# CANBUS_Pendant.net
KiCad netlist of a schematic drawn in Altium Designer
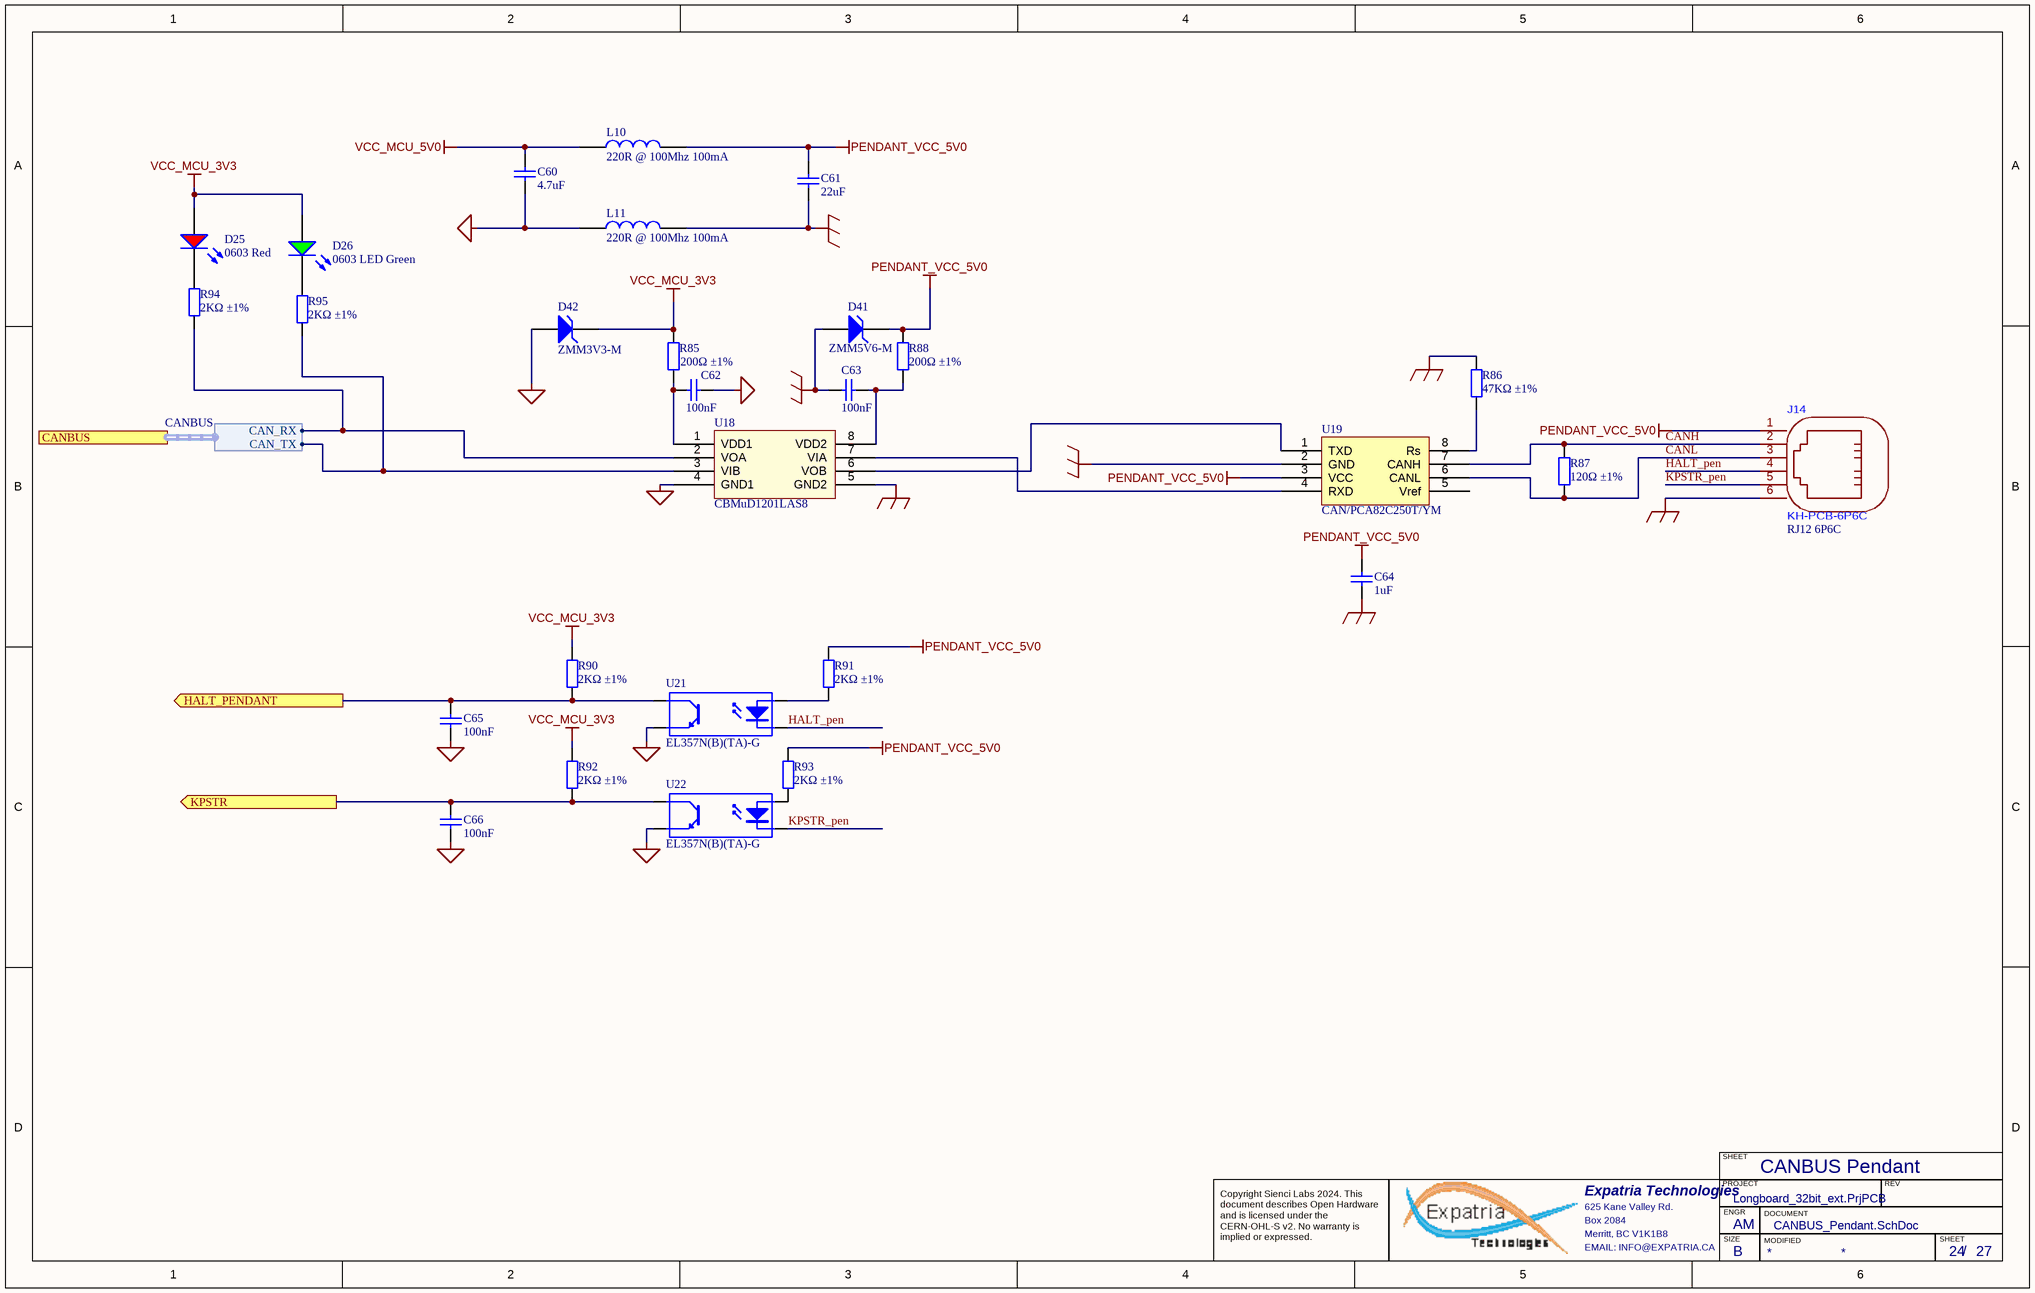
[diagram p0: CANBUS_Pendant.SchDoc]

(export (version "E")
  (design (tool "Eeschema 10.0.6"))
  (components
    (comp (ref "C60")
      (value "4.7uF")
      (footprint "0805_C")
      (description "Chip capacitors")
      (fields
        (field (name "MANUFACTURER") "Samsung Electro-Mechanics")
        (field (name "MANUFACTURER PART NUMBER") "CL21A475KAQNNNE")
      )
      (libsource (lib "Cap") (part "0805 4.7uF (475) 10% 25V"))
    )
    (comp (ref "C61")
      (value "22uF")
      (footprint "0805_C")
      (description "25V 22uF X5R ±20% 0805 Multilayer Ceramic Capacitors MLCC - SMD/SMT ROHS")
      (fields (field (name "MANUFACTURER") "Samsung Electro-Mechanics") (field (name "TOLERANCE") "20%"))
      (libsource (lib "Sienci_Labs") (part "0805 22uF (226) 20% 25V"))
    )
    (comp (ref "C62")
      (value "100nF")
      (footprint "0402_C")
      (description "16V 100nF X7R ±10% 0402 Multilayer Ceramic Capacitors MLCC - SMD/SMT ROHS")
      (fields (field (name "MANUFACTURER") "Samsung Electro-Mechanics") (field (name "TOLERANCE") "10%"))
      (libsource (lib "Sienci_Labs") (part "0402 100nF (104) 10% 16V"))
    )
    (comp (ref "C63")
      (value "100nF")
      (footprint "0402_C")
      (description "16V 100nF X7R ±10% 0402 Multilayer Ceramic Capacitors MLCC - SMD/SMT ROHS")
      (fields (field (name "MANUFACTURER") "Samsung Electro-Mechanics") (field (name "TOLERANCE") "10%"))
      (libsource (lib "Sienci_Labs") (part "0402 100nF (104) 10% 16V"))
    )
    (comp (ref "C64")
      (value "1uF")
      (footprint "0603_C")
      (description "Chip capacitors")
      (fields
        (field (name "MANUFACTURER") "Samsung Electro-Mechanics")
        (field (name "MANUFACTURER PART NUMBER") "CL10A105KB8NNNC")
      )
      (libsource (lib "Cap") (part "0603 1uF (105) 10% 50V"))
    )
    (comp (ref "C65")
      (value "100nF")
      (footprint "0603_C")
      (description "50V 100nF X7R ±10% 0603 Multilayer Ceramic Capacitors MLCC - SMD/SMT ROHS")
      (fields
        (field (name "MANUFACTURER") "YAGEO")
        (field (name "MANUFACTURER PART NUMBER") "CC0603KRX7R9BB104")
      )
      (libsource (lib "Sienci_Labs") (part "0603 100nF (104) 10% 50V"))
    )
    (comp (ref "C66")
      (value "100nF")
      (footprint "0603_C")
      (description "50V 100nF X7R ±10% 0603 Multilayer Ceramic Capacitors MLCC - SMD/SMT ROHS")
      (fields
        (field (name "MANUFACTURER") "YAGEO")
        (field (name "MANUFACTURER PART NUMBER") "CC0603KRX7R9BB104")
      )
      (libsource (lib "Sienci_Labs") (part "0603 100nF (104) 10% 50V"))
    )
    (comp (ref "D25")
      (value "0603 Red")
      (footprint "0603_LED_S1")
      (description "-40℃~+85℃ Red 0603 Light Emitting Diodes (LED) ROHS")
      (fields
        (field (name "MANUFACTURER") "Hubei KENTO Elec")
        (field (name "MANUFACTURER PART NUMBER") "KT-0603R")
      )
      (libsource (lib "Sienci_Labs") (part "KT-0603R"))
    )
    (comp (ref "D26")
      (value "0603 LED Green")
      (footprint "0603_LED_S1 - GREEN")
      (description "20mA -40℃~+85℃ 515nm~530nm Emerald 120° 60mW 0603 Light Emitting Diodes (LED) ROHS")
      (fields (field (name "MANUFACTURER PART NUMBER") "MHT192UGCT") (field (name "MANUFACTURER") "MEIHUA"))
      (libsource (lib "Sienci_Labs") (part "MHT192UGCT"))
    )
    (comp (ref "D41")
      (value "ZMM5V6-M")
      (footprint "LL-34")
      (description "Single 500mW 5.2V~6V 5.6V LL-34 Zener Diodes ROHS")
      (fields (field (name "MANUFACTURER PART NUMBER") "ZMM5V6") (field (name "MANUFACTURER") "HXY MOSFET"))
      (libsource (lib "Sienci_Labs") (part "LL-34 ZMM5V6-M"))
    )
    (comp (ref "D42")
      (value "ZMM3V3-M")
      (footprint "LL-34")
      (description "Single 3.1V~3.5V 500mW 3.3V LL-34 Zener Diodes ROHS")
      (fields (field (name "MANUFACTURER") "ST(Semtech)"))
      (libsource (lib "Sienci_Labs") (part "LL-34 ZMM3V3-M"))
    )
    (comp (ref "J14")
      (value "KH-PCB-6P6C")
      (footprint "RJ11-TH_DS1133-S60BPX")
      (fields
        (field (name "MANUFACTURER") "Shenzhen Kinghelm Elec")
        (field (name "ALTIUM_VALUE") "RJ12 6P6C")
      )
      (libsource (lib "Sienci_Labs") (part "KH-PCB-6P6C"))
    )
    (comp (ref "L10")
      (value "220R @ 100Mhz 100mA")
      (footprint "0402_L")
      (description "700mΩ ±25% 220Ω@100MHz 0402 Ferrite Beads ROHS")
      (fields
        (field (name "MANUFACTURER PART NUMBER") "CBG100505U221T")
        (field (name "MANUFACTURER") "FH (Guangdong Fenghua Advanced Tech)")
      )
      (libsource (lib "Sienci_Labs") (part "0402 220R@100Mhz 0.1A"))
    )
    (comp (ref "L11")
      (value "220R @ 100Mhz 100mA")
      (footprint "0402_L")
      (description "700mΩ ±25% 220Ω@100MHz 0402 Ferrite Beads ROHS")
      (fields
        (field (name "MANUFACTURER PART NUMBER") "CBG100505U221T")
        (field (name "MANUFACTURER") "FH (Guangdong Fenghua Advanced Tech)")
      )
      (libsource (lib "Sienci_Labs") (part "0402 220R@100Mhz 0.1A"))
    )
    (comp (ref "R85")
      (value "200Ω ±1%")
      (footprint "0402_R")
      (description "Chip resistor")
      (fields
        (field (name "MANUFACTURER") "Uniroyal Elec")
        (field (name "MANUFACTURER PART NUMBER") "0402WGF2000TCE")
      )
      (libsource (lib "RES") (part "0402 200R (2000) 1%"))
    )
    (comp (ref "R86")
      (value "47KΩ ±1%")
      (footprint "0402_R")
      (description "Chip resistor")
      (fields
        (field (name "MANUFACTURER") "Uniroyal Elec")
        (field (name "MANUFACTURER PART NUMBER") "0402WGF4702TCE")
      )
      (libsource (lib "RES") (part "0402 47K (4702) 1%"))
    )
    (comp (ref "R87")
      (value "120Ω ±1%")
      (footprint "0805_R")
      (description "Chip resistor")
      (fields
        (field (name "MANUFACTURER") "Uniroyal Elec")
        (field (name "MANUFACTURER PART NUMBER") "0805W8F1200T5E")
      )
      (libsource (lib "RES") (part "0805 120R (1200) 1%"))
    )
    (comp (ref "R88")
      (value "200Ω ±1%")
      (footprint "0402_R")
      (description "Chip resistor")
      (fields
        (field (name "MANUFACTURER") "Uniroyal Elec")
        (field (name "MANUFACTURER PART NUMBER") "0402WGF2000TCE")
      )
      (libsource (lib "RES") (part "0402 200R (2000) 1%"))
    )
    (comp (ref "R90")
      (value "2KΩ ±1%")
      (footprint "0402_R")
      (description "Chip resistor")
      (fields
        (field (name "MANUFACTURER") "Uniroyal Elec")
        (field (name "MANUFACTURER PART NUMBER") "0402WGF2001TCE")
      )
      (libsource (lib "RES") (part "0402 2K (2001) 1%"))
    )
    (comp (ref "R91")
      (value "2KΩ ±1%")
      (footprint "0402_R")
      (description "Chip resistor")
      (fields
        (field (name "MANUFACTURER") "Uniroyal Elec")
        (field (name "MANUFACTURER PART NUMBER") "0402WGF2001TCE")
      )
      (libsource (lib "RES") (part "0402 2K (2001) 1%"))
    )
    (comp (ref "R92")
      (value "2KΩ ±1%")
      (footprint "0402_R")
      (description "Chip resistor")
      (fields
        (field (name "MANUFACTURER") "Uniroyal Elec")
        (field (name "MANUFACTURER PART NUMBER") "0402WGF2001TCE")
      )
      (libsource (lib "RES") (part "0402 2K (2001) 1%"))
    )
    (comp (ref "R93")
      (value "2KΩ ±1%")
      (footprint "0402_R")
      (description "Chip resistor")
      (fields
        (field (name "MANUFACTURER") "Uniroyal Elec")
        (field (name "MANUFACTURER PART NUMBER") "0402WGF2001TCE")
      )
      (libsource (lib "RES") (part "0402 2K (2001) 1%"))
    )
    (comp (ref "R94")
      (value "2KΩ ±1%")
      (footprint "0402_R")
      (description "Chip resistor")
      (fields
        (field (name "MANUFACTURER") "Uniroyal Elec")
        (field (name "MANUFACTURER PART NUMBER") "0402WGF2001TCE")
      )
      (libsource (lib "RES") (part "0402 2K (2001) 1%"))
    )
    (comp (ref "R95")
      (value "2KΩ ±1%")
      (footprint "0402_R")
      (description "Chip resistor")
      (fields
        (field (name "MANUFACTURER") "Uniroyal Elec")
        (field (name "MANUFACTURER PART NUMBER") "0402WGF2001TCE")
      )
      (libsource (lib "RES") (part "0402 2K (2001) 1%"))
    )
    (comp (ref "U18")
      (value "CBMuD1201LAS8")
      (footprint "SOIC-8_150mil")
      (description "Dual Channel Isolator")
      (fields (field (name "MANUFACTURER") "Corebai Microelectronics"))
      (libsource (lib "Sienci_Labs") (part "CBMuD1201LAS8"))
    )
    (comp (ref "U19")
      (value "CAN/PCA82C250T/YM")
      (footprint "SOIC-8_150mil")
      (description "CAN")
      (fields
        (field (name "MANUFACTURER PART NUMBER") "PCA82C250T/YM,118")
        (field (name "MANUFACTURER") "NXP Semicon")
      )
      (libsource (lib "IC") (part "CAN/PCA82C250T/YM_[C7439]"))
    )
    (comp (ref "U21")
      (value "EL357N(B)(TA)-G")
      (footprint "Miscellaneous Devices LC:SOP-4_P2.54")
      (description "Optocoupler SOP-4, EL357N(B)(TA)-G, Everlight Electronics")
      (fields (field (name "MANUFACTURER") "Everlight"))
      (libsource (lib "Sienci_Labs") (part "EL357N(B)(TA)-G_[C6649]"))
    )
    (comp (ref "U22")
      (value "EL357N(B)(TA)-G")
      (footprint "Miscellaneous Devices LC:SOP-4_P2.54")
      (description "Optocoupler SOP-4, EL357N(B)(TA)-G, Everlight Electronics")
      (fields (field (name "MANUFACTURER") "Everlight"))
      (libsource (lib "Sienci_Labs") (part "EL357N(B)(TA)-G_[C6649]"))
    )
  )
  (nets
    (net (code "2") (name "/CANH") (class "Default")
      (node (ref "J14") (pin "2") (pinfunction "VDD_2") (pintype "passive"))
      (node (ref "R87") (pin "2") (pinfunction "2_2") (pintype "passive"))
      (node (ref "U19") (pin "7") (pinfunction "CANH_7") (pintype "passive"))
    )
    (net (code "3") (name "/CANL") (class "Default")
      (node (ref "J14") (pin "3") (pinfunction "VSS_3") (pintype "passive"))
      (node (ref "R87") (pin "1") (pinfunction "1_1") (pintype "passive"))
      (node (ref "U19") (pin "6") (pinfunction "CANL_6") (pintype "passive"))
    )
    (net (code "4") (name "/HALT_PENDANT") (class "Default")
      (node (ref "C65") (pin "2") (pinfunction "2_2") (pintype "passive"))
      (node (ref "R90") (pin "1") (pinfunction "1_1") (pintype "passive"))
      (node (ref "U21") (pin "4") (pinfunction "C_4") (pintype "passive"))
    )
    (net (code "5") (name "/HALT_pen") (class "Default")
      (node (ref "J14") (pin "4") (pinfunction "PGD_4") (pintype "passive"))
      (node (ref "U21") (pin "2") (pinfunction "K_2") (pintype "passive"))
    )
    (net (code "6") (name "/KPSTR") (class "Default")
      (node (ref "C66") (pin "2") (pinfunction "2_2") (pintype "passive"))
      (node (ref "R92") (pin "1") (pinfunction "1_1") (pintype "passive"))
      (node (ref "U22") (pin "4") (pinfunction "C_4") (pintype "passive"))
    )
    (net (code "7") (name "/KPSTR_pen") (class "Default")
      (node (ref "J14") (pin "5") (pinfunction "PGC_5") (pintype "passive"))
      (node (ref "U22") (pin "2") (pinfunction "K_2") (pintype "passive"))
    )
    (net (code "9") (name "MCU_GND") (class "Default")
      (node (ref "C60") (pin "1") (pinfunction "1_1") (pintype "passive"))
      (node (ref "C62") (pin "2") (pinfunction "2_2") (pintype "passive"))
      (node (ref "C65") (pin "1") (pinfunction "1_1") (pintype "passive"))
      (node (ref "C66") (pin "1") (pinfunction "1_1") (pintype "passive"))
      (node (ref "D42") (pin "1") (pinfunction "A_1") (pintype "passive"))
      (node (ref "L11") (pin "1") (pinfunction "1_1") (pintype "passive"))
      (node (ref "U18") (pin "4") (pinfunction "GND1_4") (pintype "passive"))
      (node (ref "U21") (pin "3") (pinfunction "E_3") (pintype "passive"))
      (node (ref "U22") (pin "3") (pinfunction "E_3") (pintype "passive"))
    )
    (net (code "10") (name "Net-(D25-PadK)") (class "Default")
      (node (ref "D25") (pin "K") (pinfunction "K_K") (pintype "passive"))
      (node (ref "R94") (pin "2") (pinfunction "2_2") (pintype "passive"))
    )
    (net (code "11") (name "Net-(D26-PadK)") (class "Default")
      (node (ref "D26") (pin "K") (pinfunction "K_K") (pintype "passive"))
      (node (ref "R95") (pin "2") (pinfunction "2_2") (pintype "passive"))
    )
    (net (code "12") (name "Net-(U18-VDD1)") (class "Default")
      (node (ref "C62") (pin "1") (pinfunction "1_1") (pintype "passive"))
      (node (ref "R85") (pin "1") (pinfunction "1_1") (pintype "passive"))
      (node (ref "U18") (pin "1") (pinfunction "VDD1_1") (pintype "passive"))
    )
    (net (code "13") (name "Net-(U18-VDD2)") (class "Default")
      (node (ref "C63") (pin "2") (pinfunction "2_2") (pintype "passive"))
      (node (ref "R88") (pin "1") (pinfunction "1_1") (pintype "passive"))
      (node (ref "U18") (pin "8") (pinfunction "VDD2_8") (pintype "passive"))
    )
    (net (code "14") (name "Net-(U18-VIA)") (class "Default")
      (node (ref "U18") (pin "7") (pinfunction "VIA_7") (pintype "passive"))
      (node (ref "U19") (pin "4") (pinfunction "RXD_4") (pintype "passive"))
    )
    (net (code "15") (name "Net-(U18-VIB)") (class "Default")
      (node (ref "R95") (pin "1") (pinfunction "1_1") (pintype "passive"))
      (node (ref "U18") (pin "3") (pinfunction "VIB_3") (pintype "passive"))
    )
    (net (code "16") (name "Net-(U18-VOA)") (class "Default")
      (node (ref "R94") (pin "1") (pinfunction "1_1") (pintype "passive"))
      (node (ref "U18") (pin "2") (pinfunction "VOA_2") (pintype "passive"))
    )
    (net (code "17") (name "Net-(U18-VOB)") (class "Default")
      (node (ref "U18") (pin "6") (pinfunction "VOB_6") (pintype "passive"))
      (node (ref "U19") (pin "1") (pinfunction "TXD_1") (pintype "passive"))
    )
    (net (code "18") (name "Net-(U19-Rs)") (class "Default")
      (node (ref "R86") (pin "1") (pinfunction "1_1") (pintype "passive"))
      (node (ref "U19") (pin "8") (pinfunction "Rs_8") (pintype "passive"))
    )
    (net (code "19") (name "Net-(U21-A)") (class "Default")
      (node (ref "R91") (pin "1") (pinfunction "1_1") (pintype "passive"))
      (node (ref "U21") (pin "1") (pinfunction "A_1") (pintype "passive"))
    )
    (net (code "20") (name "Net-(U22-A)") (class "Default")
      (node (ref "R93") (pin "1") (pinfunction "1_1") (pintype "passive"))
      (node (ref "U22") (pin "1") (pinfunction "A_1") (pintype "passive"))
    )
    (net (code "21") (name "PENDANT_VCC_5V0") (class "Default")
      (node (ref "C61") (pin "2") (pinfunction "2_2") (pintype "passive"))
      (node (ref "C64") (pin "2") (pinfunction "2_2") (pintype "passive"))
      (node (ref "D41") (pin "2") (pinfunction "K_2") (pintype "passive"))
      (node (ref "J14") (pin "1") (pinfunction "MCLR_1") (pintype "passive"))
      (node (ref "L10") (pin "2") (pinfunction "2_2") (pintype "passive"))
      (node (ref "R88") (pin "2") (pinfunction "2_2") (pintype "passive"))
      (node (ref "R91") (pin "2") (pinfunction "2_2") (pintype "passive"))
      (node (ref "R93") (pin "2") (pinfunction "2_2") (pintype "passive"))
      (node (ref "U19") (pin "3") (pinfunction "VCC_3") (pintype "passive"))
    )
    (net (code "22") (name "PEND_GND") (class "Default")
      (node (ref "C61") (pin "1") (pinfunction "1_1") (pintype "passive"))
      (node (ref "C63") (pin "1") (pinfunction "1_1") (pintype "passive"))
      (node (ref "C64") (pin "1") (pinfunction "1_1") (pintype "passive"))
      (node (ref "D41") (pin "1") (pinfunction "A_1") (pintype "passive"))
      (node (ref "J14") (pin "6") (pinfunction "NC_6") (pintype "passive"))
      (node (ref "L11") (pin "2") (pinfunction "2_2") (pintype "passive"))
      (node (ref "R86") (pin "2") (pinfunction "2_2") (pintype "passive"))
      (node (ref "U18") (pin "5") (pinfunction "GND2_5") (pintype "passive"))
      (node (ref "U19") (pin "2") (pinfunction "GND_2") (pintype "passive"))
    )
    (net (code "23") (name "VCC_MCU_3V3") (class "Default")
      (node (ref "D25") (pin "A") (pinfunction "A_A") (pintype "passive"))
      (node (ref "D26") (pin "A") (pinfunction "A_A") (pintype "passive"))
      (node (ref "D42") (pin "2") (pinfunction "K_2") (pintype "passive"))
      (node (ref "R85") (pin "2") (pinfunction "2_2") (pintype "passive"))
      (node (ref "R90") (pin "2") (pinfunction "2_2") (pintype "passive"))
      (node (ref "R92") (pin "2") (pinfunction "2_2") (pintype "passive"))
    )
    (net (code "24") (name "VCC_MCU_5V0") (class "Default")
      (node (ref "C60") (pin "2") (pinfunction "2_2") (pintype "passive"))
      (node (ref "L10") (pin "1") (pinfunction "1_1") (pintype "passive"))
    )
    (net (code "25") (name "unconnected-(U19-Vref-Pad5)") (class "Default")
      (node (ref "U19") (pin "5") (pinfunction "Vref_5") (pintype "passive"))
    )
  )
)
